# Aques_click_1_0a.net
KiCad netlist of a schematic drawn in EAGLE
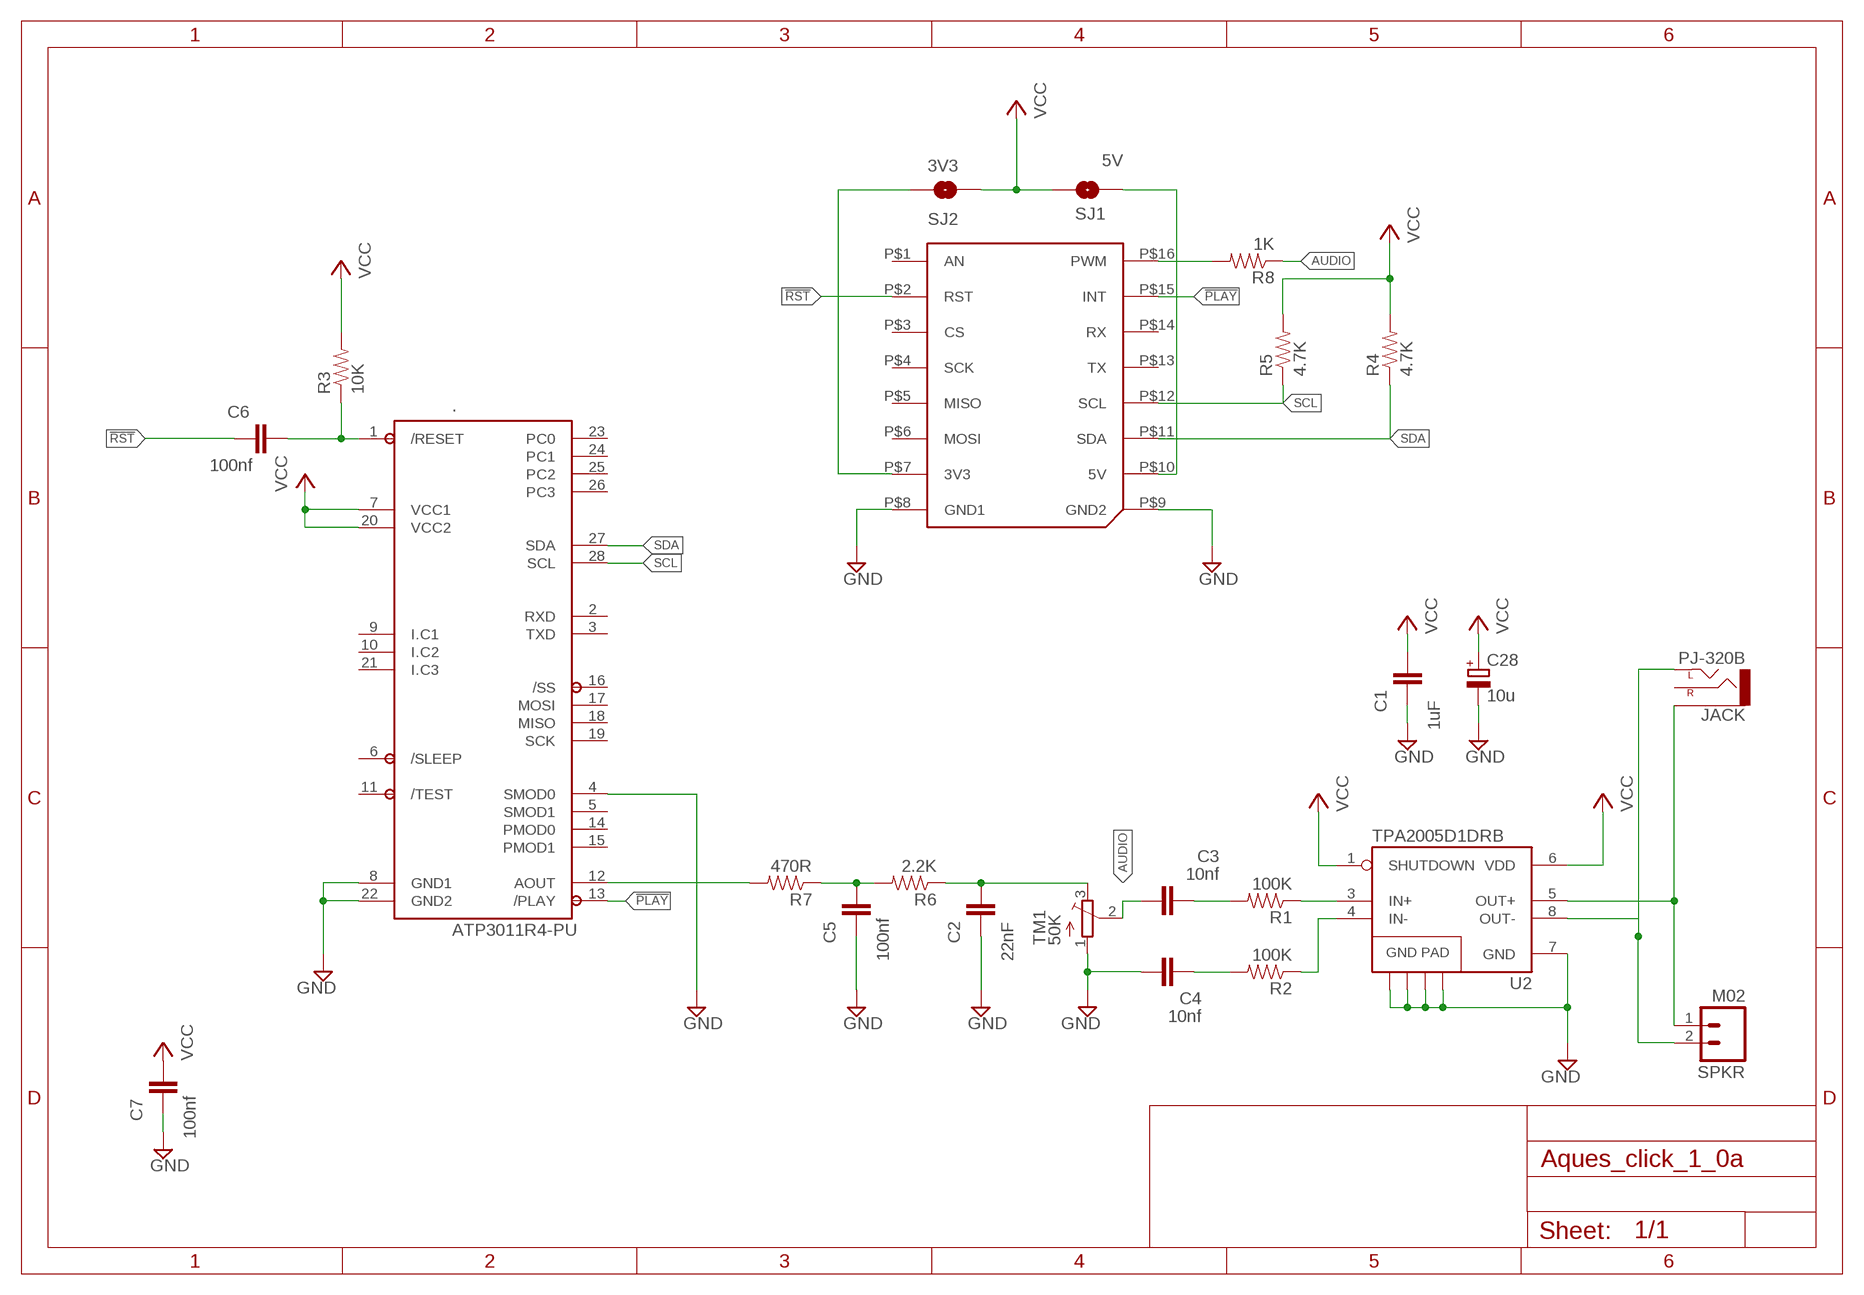
[diagram p0: schematic, sheet 1]

(export (version "E")
  (design (tool "Eeschema 10.0.6"))
  (components
    (comp (ref ".")
      (value "ATP3011R4-PU")
      (footprint "eagle-import:DIP28")
      (libsource (lib "eagle-import") (part "ATMEGA328"))
    )
    (comp (ref "C1")
      (value "1uF")
      (footprint "eagle-import:SPARKFUN_0805")
      (libsource (lib "eagle-import") (part "SPARKFUN_CAP0805"))
    )
    (comp (ref "C2")
      (value "22nF")
      (footprint "eagle-import:SPARKFUN_0805")
      (libsource (lib "eagle-import") (part "SPARKFUN_CAP0805"))
    )
    (comp (ref "C3")
      (value "10nf")
      (footprint "eagle-import:SPARKFUN_0805")
      (libsource (lib "eagle-import") (part "SPARKFUN_CAP0805"))
    )
    (comp (ref "C4")
      (value "10nf")
      (footprint "eagle-import:SPARKFUN_0805")
      (libsource (lib "eagle-import") (part "SPARKFUN_CAP0805"))
    )
    (comp (ref "C5")
      (value "100nf")
      (footprint "eagle-import:SPARKFUN_0805")
      (libsource (lib "eagle-import") (part "SPARKFUN_CAP0805"))
    )
    (comp (ref "C6")
      (value "100nf")
      (footprint "eagle-import:SPARKFUN_0805")
      (libsource (lib "eagle-import") (part "SPARKFUN_CAP0805"))
    )
    (comp (ref "C7")
      (value "100nf")
      (footprint "eagle-import:SPARKFUN_0805")
      (libsource (lib "eagle-import") (part "SPARKFUN_CAP0805"))
    )
    (comp (ref "C28")
      (value "10u")
      (footprint "eagle-import:A_3216-18R")
      (libsource (lib "eagle-import") (part "CPOL-EUA/3216-18R"))
    )
    (comp (ref "CLICK")
      (value "MIKROE_CLICKLARGE")
      (footprint "eagle-import:MIKROE_BUS_LARGE")
      (libsource (lib "eagle-import") (part "MIKROE_CLICKLARGE"))
    )
    (comp (ref "JACK")
      (value "PJ-320B")
      (footprint "eagle-import:FOOTPRINT")
      (libsource (lib "eagle-import") (part "PJ-320B"))
    )
    (comp (ref "R1")
      (value "100K")
      (footprint "eagle-import:SPARKFUN_0805")
      (libsource (lib "eagle-import") (part "SPARKFUN_RESISTOR0805-RES"))
    )
    (comp (ref "R2")
      (value "100K")
      (footprint "eagle-import:SPARKFUN_0805")
      (libsource (lib "eagle-import") (part "SPARKFUN_RESISTOR0805-RES"))
    )
    (comp (ref "R3")
      (value "10K")
      (footprint "eagle-import:SPARKFUN_0805")
      (libsource (lib "eagle-import") (part "SPARKFUN_RESISTOR0805-RES"))
    )
    (comp (ref "R4")
      (value "4.7K")
      (footprint "eagle-import:SPARKFUN_0805")
      (libsource (lib "eagle-import") (part "SPARKFUN_RESISTOR0805-RES"))
    )
    (comp (ref "R5")
      (value "4.7K")
      (footprint "eagle-import:SPARKFUN_0805")
      (libsource (lib "eagle-import") (part "SPARKFUN_RESISTOR0805-RES"))
    )
    (comp (ref "R6")
      (value "2.2K")
      (footprint "eagle-import:SPARKFUN_0805")
      (libsource (lib "eagle-import") (part "SPARKFUN_RESISTOR0805-RES"))
    )
    (comp (ref "R7")
      (value "470R")
      (footprint "eagle-import:SPARKFUN_0805")
      (libsource (lib "eagle-import") (part "SPARKFUN_RESISTOR0805-RES"))
    )
    (comp (ref "R8")
      (value "1K")
      (footprint "eagle-import:SPARKFUN_0805")
      (libsource (lib "eagle-import") (part "SPARKFUN_RESISTOR0805-RES"))
    )
    (comp (ref "SJ1")
      (value "5V")
      (footprint "eagle-import:SPARKFUN_SJ_2S-TRACE")
      (libsource (lib "eagle-import") (part "SPARKFUN_SOLDERJUMPERTRACE"))
    )
    (comp (ref "SJ2")
      (value "3V3")
      (footprint "eagle-import:SPARKFUN_SJ_2S-NO")
      (libsource (lib "eagle-import") (part "SPARKFUN_SOLDERJUMPERNO"))
    )
    (comp (ref "SPKR")
      (value "M02")
      (footprint "eagle-import:1X02_LOCK_LONGPADS")
      (libsource (lib "eagle-import") (part "M02LOCK_LONGPADS"))
    )
    (comp (ref "TM1")
      (value "50K")
      (footprint "eagle-import:TC33X")
      (libsource (lib "eagle-import") (part "TRIMPOTTC33X"))
    )
    (comp (ref "U2")
      (value "TPA2005D1DRB")
      (footprint "eagle-import:QFN-8_PAD")
      (libsource (lib "eagle-import") (part "TPA2005D1DRB"))
    )
  )
  (nets
    (net (code "1") (name "/~{PLAY}") (class "Default")
      (node (ref ".") (pin "13") (pinfunction "/PLAY_13") (pintype "bidirectional"))
      (node (ref "CLICK") (pin "P$15") (pinfunction "INT_P$15") (pintype "bidirectional"))
    )
    (net (code "2") (name "/~{RST}") (class "Default")
      (node (ref "C6") (pin "2") (pinfunction "2_2") (pintype "passive"))
      (node (ref "CLICK") (pin "P$2") (pinfunction "RST_P$2") (pintype "bidirectional"))
    )
    (net (code "3") (name "AUDIO") (class "Default")
      (node (ref "C3") (pin "1") (pinfunction "1_1") (pintype "passive"))
      (node (ref "R8") (pin "1") (pinfunction "1_1") (pintype "passive"))
      (node (ref "TM1") (pin "2") (pinfunction "S_2") (pintype "passive"))
    )
    (net (code "4") (name "GND") (class "Default")
      (node (ref ".") (pin "22") (pinfunction "GND2_22") (pintype "bidirectional"))
      (node (ref ".") (pin "4") (pinfunction "SMOD0_4") (pintype "bidirectional"))
      (node (ref ".") (pin "8") (pinfunction "GND1_8") (pintype "bidirectional"))
      (node (ref "C1") (pin "2") (pinfunction "2_2") (pintype "passive"))
      (node (ref "C2") (pin "2") (pinfunction "2_2") (pintype "passive"))
      (node (ref "C28") (pin "-") (pinfunction "-_-") (pintype "passive"))
      (node (ref "C4") (pin "1") (pinfunction "1_1") (pintype "passive"))
      (node (ref "C5") (pin "2") (pinfunction "2_2") (pintype "passive"))
      (node (ref "C7") (pin "2") (pinfunction "2_2") (pintype "passive"))
      (node (ref "CLICK") (pin "P$8") (pinfunction "GND1_P$8") (pintype "bidirectional"))
      (node (ref "CLICK") (pin "P$9") (pinfunction "GND2_P$9") (pintype "bidirectional"))
      (node (ref "TM1") (pin "1") (pinfunction "A_1") (pintype "passive"))
      (node (ref "U2") (pin "10") (pinfunction "GND_10") (pintype "power_in"))
      (node (ref "U2") (pin "11") (pinfunction "GND_11") (pintype "power_in"))
      (node (ref "U2") (pin "12") (pinfunction "GND_12") (pintype "bidirectional"))
      (node (ref "U2") (pin "13") (pinfunction "GND_13") (pintype "bidirectional"))
      (node (ref "U2") (pin "7") (pinfunction "GND_7") (pintype "power_in"))
    )
    (net (code "5") (name "Net-(.-AOUT)") (class "Default")
      (node (ref ".") (pin "12") (pinfunction "AOUT_12") (pintype "bidirectional"))
      (node (ref "R7") (pin "2") (pinfunction "2_2") (pintype "passive"))
    )
    (net (code "6") (name "Net-(.-{slash}RESET)") (class "Default")
      (node (ref ".") (pin "1") (pinfunction "/RESET_1") (pintype "bidirectional"))
      (node (ref "C6") (pin "1") (pinfunction "1_1") (pintype "passive"))
      (node (ref "R3") (pin "1") (pinfunction "1_1") (pintype "passive"))
    )
    (net (code "7") (name "Net-(C3-Pad2)") (class "Default")
      (node (ref "C3") (pin "2") (pinfunction "2_2") (pintype "passive"))
      (node (ref "R1") (pin "2") (pinfunction "2_2") (pintype "passive"))
    )
    (net (code "8") (name "Net-(C4-Pad2)") (class "Default")
      (node (ref "C4") (pin "2") (pinfunction "2_2") (pintype "passive"))
      (node (ref "R2") (pin "2") (pinfunction "2_2") (pintype "passive"))
    )
    (net (code "9") (name "Net-(C5-Pad1)") (class "Default")
      (node (ref "C5") (pin "1") (pinfunction "1_1") (pintype "passive"))
      (node (ref "R6") (pin "2") (pinfunction "2_2") (pintype "passive"))
      (node (ref "R7") (pin "1") (pinfunction "1_1") (pintype "passive"))
    )
    (net (code "10") (name "Net-(CLICK-3V3)") (class "Default")
      (node (ref "CLICK") (pin "P$7") (pinfunction "3V3_P$7") (pintype "bidirectional"))
      (node (ref "SJ2") (pin "1") (pinfunction "1_1") (pintype "passive"))
    )
    (net (code "11") (name "Net-(CLICK-5V)") (class "Default")
      (node (ref "CLICK") (pin "P$10") (pinfunction "5V_P$10") (pintype "bidirectional"))
      (node (ref "SJ1") (pin "1") (pinfunction "1_1") (pintype "passive"))
    )
    (net (code "12") (name "Net-(CLICK-PWM)") (class "Default")
      (node (ref "CLICK") (pin "P$16") (pinfunction "PWM_P$16") (pintype "bidirectional"))
      (node (ref "R8") (pin "2") (pinfunction "2_2") (pintype "passive"))
    )
    (net (code "13") (name "Net-(JACK-LEFT)") (class "Default")
      (node (ref "JACK") (pin "2") (pinfunction "LEFT_2") (pintype "bidirectional"))
      (node (ref "SPKR") (pin "2") (pinfunction "2_2") (pintype "passive"))
      (node (ref "U2") (pin "8") (pinfunction "OUT-_8") (pintype "bidirectional"))
    )
    (net (code "14") (name "Net-(JACK-SLEEVE)") (class "Default")
      (node (ref "JACK") (pin "4") (pinfunction "SLEEVE_4") (pintype "bidirectional"))
      (node (ref "SPKR") (pin "1") (pinfunction "1_1") (pintype "passive"))
      (node (ref "U2") (pin "5") (pinfunction "OUT+_5") (pintype "bidirectional"))
    )
    (net (code "15") (name "Net-(TM1-E)") (class "Default")
      (node (ref "C2") (pin "1") (pinfunction "1_1") (pintype "passive"))
      (node (ref "R6") (pin "1") (pinfunction "1_1") (pintype "passive"))
      (node (ref "TM1") (pin "3") (pinfunction "E_3") (pintype "passive"))
    )
    (net (code "16") (name "Net-(U2-IN+)") (class "Default")
      (node (ref "R1") (pin "1") (pinfunction "1_1") (pintype "passive"))
      (node (ref "U2") (pin "3") (pinfunction "IN+_3") (pintype "bidirectional"))
    )
    (net (code "17") (name "Net-(U2-IN-)") (class "Default")
      (node (ref "R2") (pin "1") (pinfunction "1_1") (pintype "passive"))
      (node (ref "U2") (pin "4") (pinfunction "IN-_4") (pintype "bidirectional"))
    )
    (net (code "18") (name "SCL") (class "Default")
      (node (ref ".") (pin "28") (pinfunction "SCL_28") (pintype "bidirectional"))
      (node (ref "CLICK") (pin "P$12") (pinfunction "SCL_P$12") (pintype "bidirectional"))
      (node (ref "R5") (pin "1") (pinfunction "1_1") (pintype "passive"))
    )
    (net (code "19") (name "SDA") (class "Default")
      (node (ref ".") (pin "27") (pinfunction "SDA_27") (pintype "bidirectional"))
      (node (ref "CLICK") (pin "P$11") (pinfunction "SDA_P$11") (pintype "bidirectional"))
      (node (ref "R4") (pin "1") (pinfunction "1_1") (pintype "passive"))
    )
    (net (code "20") (name "VCC") (class "Default")
      (node (ref ".") (pin "20") (pinfunction "VCC2_20") (pintype "bidirectional"))
      (node (ref ".") (pin "7") (pinfunction "VCC1_7") (pintype "bidirectional"))
      (node (ref "C1") (pin "1") (pinfunction "1_1") (pintype "passive"))
      (node (ref "C28") (pin "+") (pinfunction "+_+") (pintype "passive"))
      (node (ref "C7") (pin "1") (pinfunction "1_1") (pintype "passive"))
      (node (ref "R3") (pin "2") (pinfunction "2_2") (pintype "passive"))
      (node (ref "R4") (pin "2") (pinfunction "2_2") (pintype "passive"))
      (node (ref "R5") (pin "2") (pinfunction "2_2") (pintype "passive"))
      (node (ref "SJ1") (pin "2") (pinfunction "2_2") (pintype "passive"))
      (node (ref "SJ2") (pin "2") (pinfunction "2_2") (pintype "passive"))
      (node (ref "U2") (pin "1") (pinfunction "SHUTDOWN_1") (pintype "input"))
      (node (ref "U2") (pin "6") (pinfunction "VDD_6") (pintype "power_in"))
    )
    (net (code "21") (name "unconnected-(.-I.C1-Pad9)") (class "Default")
      (node (ref ".") (pin "9") (pinfunction "I.C1_9") (pintype "bidirectional"))
    )
    (net (code "22") (name "unconnected-(.-I.C2-Pad10)") (class "Default")
      (node (ref ".") (pin "10") (pinfunction "I.C2_10") (pintype "bidirectional"))
    )
    (net (code "23") (name "unconnected-(.-I.C3-Pad21)") (class "Default")
      (node (ref ".") (pin "21") (pinfunction "I.C3_21") (pintype "bidirectional"))
    )
    (net (code "24") (name "unconnected-(.-MISO-Pad18)") (class "Default")
      (node (ref ".") (pin "18") (pinfunction "MISO_18") (pintype "bidirectional"))
    )
    (net (code "25") (name "unconnected-(.-MOSI-Pad17)") (class "Default")
      (node (ref ".") (pin "17") (pinfunction "MOSI_17") (pintype "bidirectional"))
    )
    (net (code "26") (name "unconnected-(.-PC0-Pad23)") (class "Default")
      (node (ref ".") (pin "23") (pinfunction "PC0_23") (pintype "bidirectional"))
    )
    (net (code "27") (name "unconnected-(.-PC1-Pad24)") (class "Default")
      (node (ref ".") (pin "24") (pinfunction "PC1_24") (pintype "bidirectional"))
    )
    (net (code "28") (name "unconnected-(.-PC2-Pad25)") (class "Default")
      (node (ref ".") (pin "25") (pinfunction "PC2_25") (pintype "bidirectional"))
    )
    (net (code "29") (name "unconnected-(.-PC3-Pad26)") (class "Default")
      (node (ref ".") (pin "26") (pinfunction "PC3_26") (pintype "bidirectional"))
    )
    (net (code "30") (name "unconnected-(.-PMOD0-Pad14)") (class "Default")
      (node (ref ".") (pin "14") (pinfunction "PMOD0_14") (pintype "bidirectional"))
    )
    (net (code "31") (name "unconnected-(.-PMOD1-Pad15)") (class "Default")
      (node (ref ".") (pin "15") (pinfunction "PMOD1_15") (pintype "bidirectional"))
    )
    (net (code "32") (name "unconnected-(.-RXD-Pad2)") (class "Default")
      (node (ref ".") (pin "2") (pinfunction "RXD_2") (pintype "bidirectional"))
    )
    (net (code "33") (name "unconnected-(.-SCK-Pad19)") (class "Default")
      (node (ref ".") (pin "19") (pinfunction "SCK_19") (pintype "bidirectional"))
    )
    (net (code "34") (name "unconnected-(.-SMOD1-Pad5)") (class "Default")
      (node (ref ".") (pin "5") (pinfunction "SMOD1_5") (pintype "bidirectional"))
    )
    (net (code "35") (name "unconnected-(.-TXD-Pad3)") (class "Default")
      (node (ref ".") (pin "3") (pinfunction "TXD_3") (pintype "bidirectional"))
    )
    (net (code "36") (name "unconnected-(.-{slash}SLEEP-Pad6)") (class "Default")
      (node (ref ".") (pin "6") (pinfunction "/SLEEP_6") (pintype "bidirectional"))
    )
    (net (code "37") (name "unconnected-(.-{slash}SS-Pad16)") (class "Default")
      (node (ref ".") (pin "16") (pinfunction "/SS_16") (pintype "bidirectional"))
    )
    (net (code "38") (name "unconnected-(.-{slash}TEST-Pad11)") (class "Default")
      (node (ref ".") (pin "11") (pinfunction "/TEST_11") (pintype "bidirectional"))
    )
    (net (code "39") (name "unconnected-(CLICK-AN-PadP$1)") (class "Default")
      (node (ref "CLICK") (pin "P$1") (pinfunction "AN_P$1") (pintype "bidirectional"))
    )
    (net (code "40") (name "unconnected-(CLICK-CS-PadP$3)") (class "Default")
      (node (ref "CLICK") (pin "P$3") (pinfunction "CS_P$3") (pintype "bidirectional"))
    )
    (net (code "41") (name "unconnected-(CLICK-MISO-PadP$5)") (class "Default")
      (node (ref "CLICK") (pin "P$5") (pinfunction "MISO_P$5") (pintype "bidirectional"))
    )
    (net (code "42") (name "unconnected-(CLICK-MOSI-PadP$6)") (class "Default")
      (node (ref "CLICK") (pin "P$6") (pinfunction "MOSI_P$6") (pintype "bidirectional"))
    )
    (net (code "43") (name "unconnected-(CLICK-RX-PadP$14)") (class "Default")
      (node (ref "CLICK") (pin "P$14") (pinfunction "RX_P$14") (pintype "bidirectional"))
    )
    (net (code "44") (name "unconnected-(CLICK-SCK-PadP$4)") (class "Default")
      (node (ref "CLICK") (pin "P$4") (pinfunction "SCK_P$4") (pintype "bidirectional"))
    )
    (net (code "45") (name "unconnected-(CLICK-TX-PadP$13)") (class "Default")
      (node (ref "CLICK") (pin "P$13") (pinfunction "TX_P$13") (pintype "bidirectional"))
    )
    (net (code "46") (name "unconnected-(JACK-RIGHT-Pad3)") (class "Default")
      (node (ref "JACK") (pin "3") (pinfunction "RIGHT_3") (pintype "bidirectional"))
    )
  )
)
